# Transmitter_PCB.net
KiCad netlist of a schematic drawn in Altium Designer
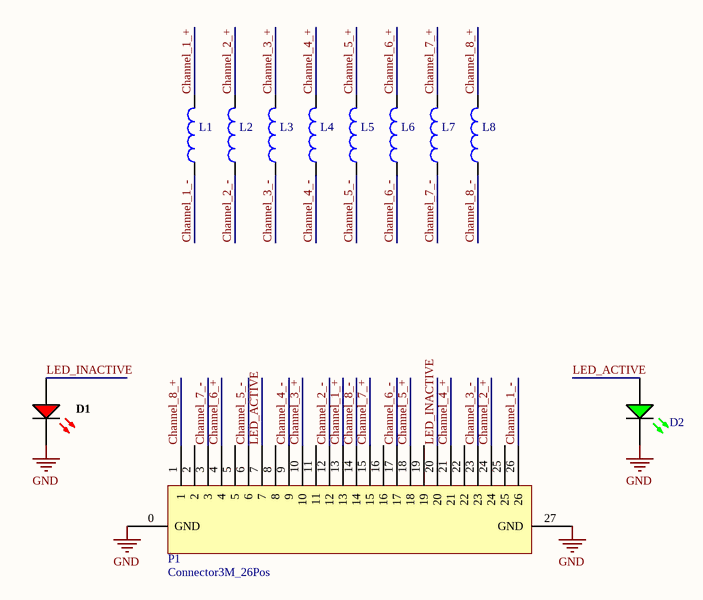
[diagram p0: Transmitter_PCB.SchDoc]

(export (version "E")
  (design (tool "Eeschema 10.0.6"))
  (components
    (comp (ref "D1")
      (value "KPA-3010SECK-J3")
      (footprint "KING-LED2107-13-RED-2_V")
      (description "KINGBRIGHT - KPA-3010SECK-J3 - LED, 1104, RIGHT AN., RED, 380MCD")
      (fields (field (name "MANUFACTURER") "KINGBRIGHT"))
      (libsource (lib "Transmitter_PCB") (part "KPA-3010SECK-J3"))
    )
    (comp (ref "D2")
      (value "KPA-3010ZGCK")
      (footprint "KING-LED2107-13-RED-2_V")
      (description "KINGBRIGHT - KPA-3010ZGCK - LED, 3MM, GREEN, 300MCD, 525NM")
      (fields (field (name "MANUFACTURER") "KINGBRIGHT"))
      (libsource (lib "Transmitter_PCB") (part "KPA-3010ZGCK"))
    )
    (comp (ref "L1")
      (value "~")
      (footprint "TRANSMITTER_COIL_UCC_ORIGINAL")
      (description "TRANSMITTER_COIL_UCC_ORIGINAL")
      (libsource (lib "Transmitter_PCB") (part "TRANSMITTER_COIL_UCC_ORIGINAL"))
    )
    (comp (ref "L2")
      (value "~")
      (footprint "TRANSMITTER_COIL_UCC_ORIGINAL")
      (description "TRANSMITTER_COIL_UCC_ORIGINAL")
      (libsource (lib "Transmitter_PCB") (part "TRANSMITTER_COIL_UCC_ORIGINAL"))
    )
    (comp (ref "L3")
      (value "~")
      (footprint "TRANSMITTER_COIL_UCC_ORIGINAL")
      (description "TRANSMITTER_COIL_UCC_ORIGINAL")
      (libsource (lib "Transmitter_PCB") (part "TRANSMITTER_COIL_UCC_ORIGINAL"))
    )
    (comp (ref "L4")
      (value "~")
      (footprint "TRANSMITTER_COIL_UCC_ORIGINAL")
      (description "TRANSMITTER_COIL_UCC_ORIGINAL")
      (libsource (lib "Transmitter_PCB") (part "TRANSMITTER_COIL_UCC_ORIGINAL"))
    )
    (comp (ref "L5")
      (value "~")
      (footprint "TRANSMITTER_COIL_UCC_ORIGINAL")
      (description "TRANSMITTER_COIL_UCC_ORIGINAL")
      (libsource (lib "Transmitter_PCB") (part "TRANSMITTER_COIL_UCC_ORIGINAL"))
    )
    (comp (ref "L6")
      (value "~")
      (footprint "TRANSMITTER_COIL_UCC_ORIGINAL")
      (description "TRANSMITTER_COIL_UCC_ORIGINAL")
      (libsource (lib "Transmitter_PCB") (part "TRANSMITTER_COIL_UCC_ORIGINAL"))
    )
    (comp (ref "L7")
      (value "~")
      (footprint "TRANSMITTER_COIL_UCC_ORIGINAL")
      (description "TRANSMITTER_COIL_UCC_ORIGINAL")
      (libsource (lib "Transmitter_PCB") (part "TRANSMITTER_COIL_UCC_ORIGINAL"))
    )
    (comp (ref "L8")
      (value "~")
      (footprint "TRANSMITTER_COIL_UCC_ORIGINAL")
      (description "TRANSMITTER_COIL_UCC_ORIGINAL")
      (libsource (lib "Transmitter_PCB") (part "TRANSMITTER_COIL_UCC_ORIGINAL"))
    )
    (comp (ref "P1")
      (value "Connector3M_26Pos")
      (footprint "Connector_3M_26Pos")
      (fields (field (name "PUBLISHER") "Altium Limited"))
      (libsource (lib "Transmitter_PCB") (part "Connector3M_26Pos"))
    )
  )
  (nets
    (net (code "1") (name "/Channel_1_+") (class "Default")
      (node (ref "L1") (pin "2") (pinfunction "2_2") (pintype "passive"))
      (node (ref "P1") (pin "13") (pinfunction "13_13") (pintype "passive"))
    )
    (net (code "2") (name "/Channel_1_-") (class "Default")
      (node (ref "L1") (pin "1") (pinfunction "1_1") (pintype "passive"))
      (node (ref "P1") (pin "26") (pinfunction "26_26") (pintype "passive"))
    )
    (net (code "3") (name "/Channel_2_+") (class "Default")
      (node (ref "L2") (pin "2") (pinfunction "2_2") (pintype "passive"))
      (node (ref "P1") (pin "24") (pinfunction "24_24") (pintype "passive"))
    )
    (net (code "4") (name "/Channel_2_-") (class "Default")
      (node (ref "L2") (pin "1") (pinfunction "1_1") (pintype "passive"))
      (node (ref "P1") (pin "12") (pinfunction "12_12") (pintype "passive"))
    )
    (net (code "5") (name "/Channel_3_+") (class "Default")
      (node (ref "L3") (pin "2") (pinfunction "2_2") (pintype "passive"))
      (node (ref "P1") (pin "10") (pinfunction "10_10") (pintype "passive"))
    )
    (net (code "6") (name "/Channel_3_-") (class "Default")
      (node (ref "L3") (pin "1") (pinfunction "1_1") (pintype "passive"))
      (node (ref "P1") (pin "23") (pinfunction "23_23") (pintype "passive"))
    )
    (net (code "7") (name "/Channel_4_+") (class "Default")
      (node (ref "L4") (pin "2") (pinfunction "2_2") (pintype "passive"))
      (node (ref "P1") (pin "21") (pinfunction "21_21") (pintype "passive"))
    )
    (net (code "8") (name "/Channel_4_-") (class "Default")
      (node (ref "L4") (pin "1") (pinfunction "1_1") (pintype "passive"))
      (node (ref "P1") (pin "9") (pinfunction "9_9") (pintype "passive"))
    )
    (net (code "9") (name "/Channel_5_+") (class "Default")
      (node (ref "L5") (pin "2") (pinfunction "2_2") (pintype "passive"))
      (node (ref "P1") (pin "18") (pinfunction "18_18") (pintype "passive"))
    )
    (net (code "10") (name "/Channel_5_-") (class "Default")
      (node (ref "L5") (pin "1") (pinfunction "1_1") (pintype "passive"))
      (node (ref "P1") (pin "6") (pinfunction "6_6") (pintype "passive"))
    )
    (net (code "11") (name "/Channel_6_+") (class "Default")
      (node (ref "L6") (pin "2") (pinfunction "2_2") (pintype "passive"))
      (node (ref "P1") (pin "4") (pinfunction "4_4") (pintype "passive"))
    )
    (net (code "12") (name "/Channel_6_-") (class "Default")
      (node (ref "L6") (pin "1") (pinfunction "1_1") (pintype "passive"))
      (node (ref "P1") (pin "17") (pinfunction "17_17") (pintype "passive"))
    )
    (net (code "13") (name "/Channel_7_+") (class "Default")
      (node (ref "L7") (pin "2") (pinfunction "2_2") (pintype "passive"))
      (node (ref "P1") (pin "15") (pinfunction "15_15") (pintype "passive"))
    )
    (net (code "14") (name "/Channel_7_-") (class "Default")
      (node (ref "L7") (pin "1") (pinfunction "1_1") (pintype "passive"))
      (node (ref "P1") (pin "3") (pinfunction "3_3") (pintype "passive"))
    )
    (net (code "15") (name "/Channel_8_+") (class "Default")
      (node (ref "L8") (pin "2") (pinfunction "2_2") (pintype "passive"))
      (node (ref "P1") (pin "1") (pinfunction "1_1") (pintype "passive"))
    )
    (net (code "16") (name "/Channel_8_-") (class "Default")
      (node (ref "L8") (pin "1") (pinfunction "1_1") (pintype "passive"))
      (node (ref "P1") (pin "14") (pinfunction "14_14") (pintype "passive"))
    )
    (net (code "17") (name "/LED_ACTIVE") (class "Default")
      (node (ref "D2") (pin "2") (pinfunction "A_2") (pintype "passive"))
      (node (ref "P1") (pin "7") (pinfunction "7_7") (pintype "passive"))
    )
    (net (code "18") (name "/LED_INACTIVE") (class "Default")
      (node (ref "D1") (pin "2") (pinfunction "A_2") (pintype "passive"))
      (node (ref "P1") (pin "20") (pinfunction "20_20") (pintype "passive"))
    )
    (net (code "19") (name "GND") (class "Default")
      (node (ref "D1") (pin "1") (pinfunction "K_1") (pintype "passive"))
      (node (ref "D2") (pin "1") (pinfunction "K_1") (pintype "passive"))
      (node (ref "P1") (pin "0") (pinfunction "GND_0") (pintype "passive"))
      (node (ref "P1") (pin "27") (pinfunction "GND_27") (pintype "passive"))
    )
    (net (code "20") (name "unconnected-(P1-Pad2)") (class "Default")
      (node (ref "P1") (pin "2") (pinfunction "2_2") (pintype "passive"))
    )
    (net (code "21") (name "unconnected-(P1-Pad5)") (class "Default")
      (node (ref "P1") (pin "5") (pinfunction "5_5") (pintype "passive"))
    )
    (net (code "22") (name "unconnected-(P1-Pad8)") (class "Default")
      (node (ref "P1") (pin "8") (pinfunction "8_8") (pintype "passive"))
    )
    (net (code "23") (name "unconnected-(P1-Pad11)") (class "Default")
      (node (ref "P1") (pin "11") (pinfunction "11_11") (pintype "passive"))
    )
    (net (code "24") (name "unconnected-(P1-Pad16)") (class "Default")
      (node (ref "P1") (pin "16") (pinfunction "16_16") (pintype "passive"))
    )
    (net (code "25") (name "unconnected-(P1-Pad19)") (class "Default")
      (node (ref "P1") (pin "19") (pinfunction "19_19") (pintype "passive"))
    )
    (net (code "26") (name "unconnected-(P1-Pad22)") (class "Default")
      (node (ref "P1") (pin "22") (pinfunction "22_22") (pintype "passive"))
    )
    (net (code "27") (name "unconnected-(P1-Pad25)") (class "Default")
      (node (ref "P1") (pin "25") (pinfunction "25_25") (pintype "passive"))
    )
  )
)
